# RECEPTOR_AIS_HF_R00.net
KiCad netlist of a schematic drawn in Altium Designer
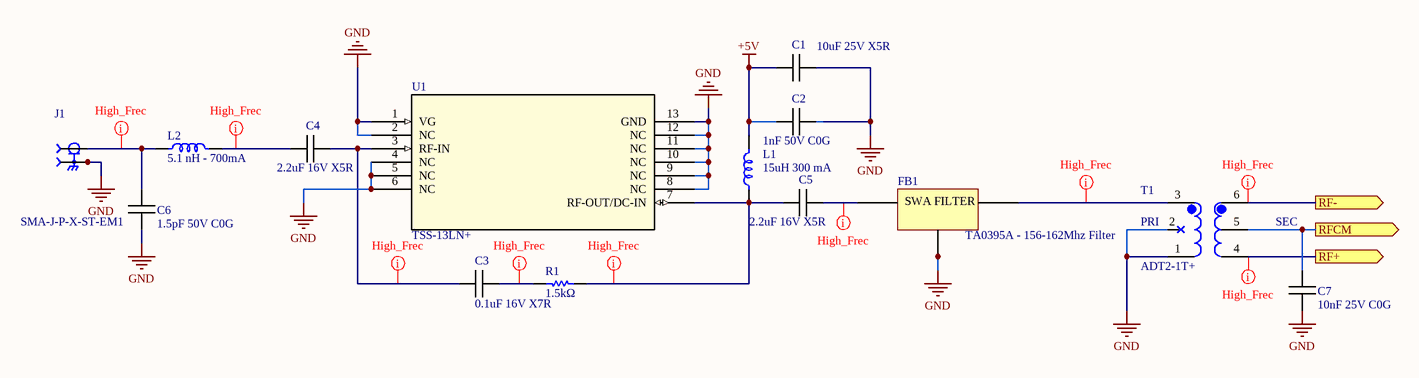
[diagram p0: RECEPTOR_AIS_HF_R00.SchDoc]

(export (version "E")
  (design (tool "Eeschema 10.0.6"))
  (components
    (comp (ref "C1")
      (value "10uF 25V X5R")
      (footprint "C_0805")
      (description "10 µF ±10% 25V Ceramic Capacitor X5R 0805 (2012 Metric)")
      (libsource (lib "RECEPTOR_AIS_R00") (part "Capacitor NP"))
    )
    (comp (ref "C2")
      (value "1nF 50V C0G")
      (footprint "C_0603")
      (description "1000 pF ±5% 50V Ceramic Capacitor C0G, NP0 0603 (1608 Metric)")
      (libsource (lib "RECEPTOR_AIS_R00") (part "Capacitor NP"))
    )
    (comp (ref "C3")
      (value "0.1uF 16V X7R")
      (footprint "C_0603")
      (description "0.1 µF ±10% 16V Ceramic Capacitor X7R 0603 (1608 Metric)")
      (libsource (lib "RECEPTOR_AIS_R00") (part "Capacitor NP"))
    )
    (comp (ref "C4")
      (value "2.2uF 16V X5R")
      (footprint "C_0603")
      (description "2.2 µF ±10% 16V Ceramic Capacitor X5R 0603 (1608 Metric)")
      (libsource (lib "RECEPTOR_AIS_R00") (part "Capacitor NP"))
    )
    (comp (ref "C5")
      (value "2.2uF 16V X5R")
      (footprint "C_0603")
      (description "2.2 µF ±10% 16V Ceramic Capacitor X5R 0603 (1608 Metric)")
      (libsource (lib "RECEPTOR_AIS_R00") (part "Capacitor NP"))
    )
    (comp (ref "C6")
      (value "1.5pF 50V C0G")
      (footprint "C_0603")
      (description "1.5 pF ±0.25pF 50V Ceramic Capacitor C0G, NP0 0603 (1608 Metric)")
      (libsource (lib "RECEPTOR_AIS_R00") (part "Capacitor NP"))
    )
    (comp (ref "C7")
      (value "10nF 25V C0G")
      (footprint "C_0603")
      (description "10000 pF ±5% 25V Ceramic Capacitor C0G, NP0 0603 (1608 Metric)")
      (libsource (lib "RECEPTOR_AIS_R00") (part "Capacitor NP"))
    )
    (comp (ref "FB1")
      (value "TA0395A - 156-162Mhz Filter")
      (footprint "TA0395A")
      (libsource (lib "RECEPTOR_AIS_R00") (part "TA0395A"))
    )
    (comp (ref "J1")
      (value "SMA-J-P-X-ST-EM1")
      (footprint "CONN_SMA-J-P-H-ST-EM1_SAI")
      (description "SMA Connector Jack, Female Socket 50 Ohms Board Edge, Cutout; Surface Mount Solder")
      (fields (field (name "MF") "Samtec") (field (name "MP") "SMA-J-P-H-ST-EM3"))
      (libsource (lib "RECEPTOR_AIS_R00") (part "SMA-J-P-X-ST-EM1"))
    )
    (comp (ref "L1")
      (value "15uH 300 mA")
      (footprint "IND_LQH32DN150K53L")
      (description "LQH32DN150K53L - 15 µH Unshielded Drum Core, Wirewound Inductor 300 mA 754mOhm Max Nonstandard")
      (libsource (lib "Tp_Integrador_R00") (part "IND"))
    )
    (comp (ref "L2")
      (value "5.1 nH - 700mA")
      (footprint "L_0603")
      (description "LQW18AS5N1J00D - 5.1 nH Unshielded Wirewound Inductor 700 mA 140mOhm Max 0603 (1608 Metric)")
      (libsource (lib "Tp_Integrador_R00") (part "IND"))
    )
    (comp (ref "R1")
      (value "1.5kΩ")
      (footprint "R_0603")
      (description "1.5 kΩ ±1% 0.1W, 1/10W Chip Resistor 0603 (1608 Metric) Moisture Resistant Thick Film")
      (libsource (lib "Tp_Integrador_R00") (part "Res1"))
    )
    (comp (ref "T1")
      (value "ADT2-1T+")
      (footprint "CD542_MNC")
      (description "Description")
      (fields (field (name "COPYRIGHT") "Copyright (C) 2026 Ultra Librarian. All rights reserved."))
      (libsource (lib "RECEPTOR_AIS_R00") (part "ADT2-1T+"))
    )
    (comp (ref "U1")
      (value "TSS-13LN+")
      (footprint "TSS-13LN+")
      (description "Description")
      (fields (field (name "COPYRIGHT") "Copyright (C) 2025 Ultra Librarian. All rights reserved."))
      (libsource (lib "RECEPTOR_AIS_R00") (part "TSS-13LN+"))
    )
  )
  (nets
    (net (code "1") (name "+5V") (class "Default")
      (node (ref "C1") (pin "2") (pinfunction "2_2") (pintype "passive"))
      (node (ref "C2") (pin "1") (pinfunction "1_1") (pintype "passive"))
      (node (ref "L1") (pin "2") (pinfunction "2_2") (pintype "passive"))
    )
    (net (code "2") (name "/RF+") (class "Default")
      (node (ref "T1") (pin "4") (pinfunction "4_4") (pintype "passive"))
    )
    (net (code "3") (name "/RF-") (class "Default")
      (node (ref "T1") (pin "6") (pinfunction "6_6") (pintype "passive"))
    )
    (net (code "4") (name "/RFCM") (class "Default")
      (node (ref "C7") (pin "2") (pinfunction "2_2") (pintype "passive"))
      (node (ref "T1") (pin "5") (pinfunction "5_5") (pintype "passive"))
    )
    (net (code "5") (name "GND") (class "Default")
      (node (ref "C1") (pin "1") (pinfunction "1_1") (pintype "passive"))
      (node (ref "C2") (pin "2") (pinfunction "2_2") (pintype "passive"))
      (node (ref "C6") (pin "1") (pinfunction "1_1") (pintype "passive"))
      (node (ref "C7") (pin "1") (pinfunction "1_1") (pintype "passive"))
      (node (ref "FB1") (pin "1") (pinfunction "1_1") (pintype "passive"))
      (node (ref "FB1") (pin "10") (pinfunction "10_10") (pintype "passive"))
      (node (ref "FB1") (pin "3") (pinfunction "3_3") (pintype "passive"))
      (node (ref "FB1") (pin "4") (pinfunction "4_4") (pintype "passive"))
      (node (ref "FB1") (pin "5") (pinfunction "5_5") (pintype "passive"))
      (node (ref "FB1") (pin "6") (pinfunction "6_6") (pintype "passive"))
      (node (ref "FB1") (pin "8") (pinfunction "8_8") (pintype "passive"))
      (node (ref "FB1") (pin "9") (pinfunction "9_9") (pintype "passive"))
      (node (ref "J1") (pin "2") (pinfunction "2_2") (pintype "passive"))
      (node (ref "J1") (pin "3") (pinfunction "2_3") (pintype "passive"))
      (node (ref "T1") (pin "1") (pinfunction "1_1") (pintype "passive"))
      (node (ref "T1") (pin "2") (pinfunction "2_2") (pintype "passive"))
      (node (ref "U1") (pin "1") (pinfunction "VG_1") (pintype "input"))
      (node (ref "U1") (pin "10") (pinfunction "NC_10") (pintype "passive"))
      (node (ref "U1") (pin "11") (pinfunction "NC_11") (pintype "passive"))
      (node (ref "U1") (pin "12") (pinfunction "NC_12") (pintype "passive"))
      (node (ref "U1") (pin "13") (pinfunction "GND_13") (pintype "power_in"))
      (node (ref "U1") (pin "2") (pinfunction "NC_2") (pintype "passive"))
      (node (ref "U1") (pin "4") (pinfunction "NC_4") (pintype "passive"))
      (node (ref "U1") (pin "5") (pinfunction "NC_5") (pintype "passive"))
      (node (ref "U1") (pin "6") (pinfunction "NC_6") (pintype "passive"))
      (node (ref "U1") (pin "8") (pinfunction "NC_8") (pintype "passive"))
      (node (ref "U1") (pin "9") (pinfunction "NC_9") (pintype "passive"))
    )
    (net (code "6") (name "Net-(C3-Pad2)") (class "Default")
      (node (ref "C3") (pin "2") (pinfunction "2_2") (pintype "passive"))
      (node (ref "R1") (pin "2") (pinfunction "2_2") (pintype "passive"))
    )
    (net (code "7") (name "Net-(C4-Pad1)") (class "Default")
      (node (ref "C4") (pin "1") (pinfunction "1_1") (pintype "passive"))
      (node (ref "L2") (pin "2") (pinfunction "2_2") (pintype "passive"))
    )
    (net (code "8") (name "Net-(C5-Pad2)") (class "Default")
      (node (ref "C5") (pin "2") (pinfunction "2_2") (pintype "passive"))
      (node (ref "FB1") (pin "7") (pinfunction "7_7") (pintype "passive"))
    )
    (net (code "9") (name "Net-(C6-Pad2)") (class "Default")
      (node (ref "C6") (pin "2") (pinfunction "2_2") (pintype "passive"))
      (node (ref "J1") (pin "1") (pinfunction "1_1") (pintype "passive"))
      (node (ref "L2") (pin "1") (pinfunction "1_1") (pintype "passive"))
    )
    (net (code "10") (name "Net-(FB1-Pad2)") (class "Default")
      (node (ref "FB1") (pin "2") (pinfunction "2_2") (pintype "passive"))
      (node (ref "T1") (pin "3") (pinfunction "3_3") (pintype "passive"))
    )
    (net (code "11") (name "Net-(U1-RF-IN)") (class "Default")
      (node (ref "C3") (pin "1") (pinfunction "1_1") (pintype "passive"))
      (node (ref "C4") (pin "2") (pinfunction "2_2") (pintype "passive"))
      (node (ref "U1") (pin "3") (pinfunction "RF-IN_3") (pintype "input"))
    )
    (net (code "12") (name "Net-(U1-RF-OUT{slash}DC-IN)") (class "Default")
      (node (ref "C5") (pin "1") (pinfunction "1_1") (pintype "passive"))
      (node (ref "L1") (pin "1") (pinfunction "1_1") (pintype "passive"))
      (node (ref "R1") (pin "1") (pinfunction "1_1") (pintype "passive"))
      (node (ref "U1") (pin "7") (pinfunction "RF-OUT/DC-IN_7") (pintype "bidirectional"))
    )
  )
)
